# ESP8266.net
KiCad netlist of a schematic drawn in Altium Designer
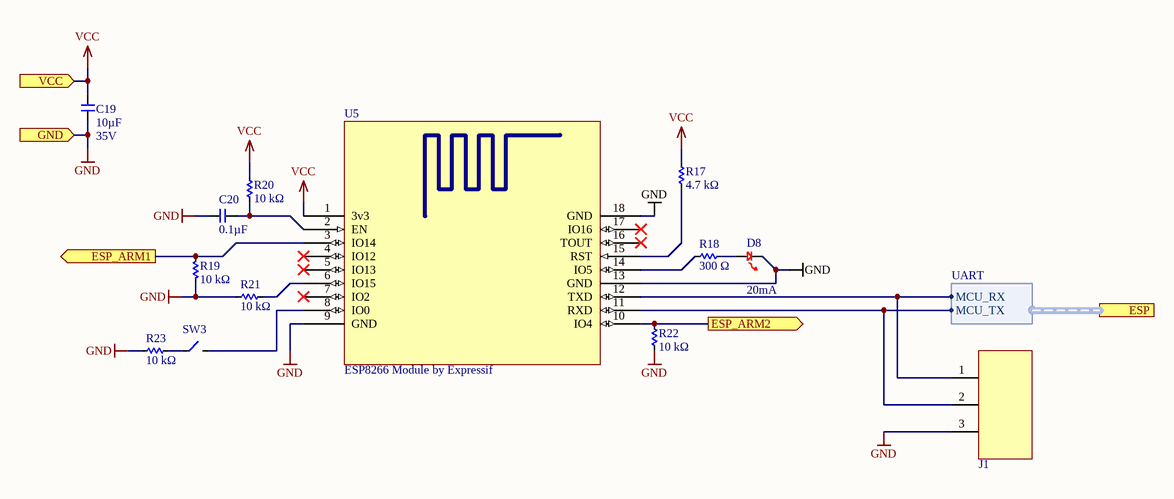
[diagram p0: ESP8266.SchDoc]

(export (version "E")
  (design (tool "Eeschema 10.0.6"))
  (components
    (comp (ref "C19")
      (value "__template_cap")
      (footprint "C0603")
      (description "CAP CER 10UF 35V X5R 0603 20%")
      (fields
        (field (name "CAPACITANCE (SHORTHAND)") "10µF")
        (field (name "RATED VOLTAGE") "35V")
        (field (name "MANUFACTURER") "Murata Electronics North America")
      )
      (libsource (lib "passives") (part "__template_cap"))
    )
    (comp (ref "C20")
      (value "__template_cap")
      (footprint "C0603")
      (fields
        (field (name "CAPACITANCE (SHORTHAND)") "0.1µF")
        (field (name "MANUFACTURER") "Murata Electronics North America")
      )
      (libsource (lib "passives") (part "__template_cap"))
    )
    (comp (ref "D8")
      (value "RED")
      (footprint "0805_Diode")
      (description "LED 0805 RED 20MA")
      (fields
        (field (name "MANUFACTURER") "OSRAM Opto Semiconductors Inc")
        (field (name "MANUFACTURER PART NUMBER") "LH R974-LP-1")
        (field (name "CURRENT - TEST") "20mA")
      )
      (libsource (lib "SSI") (part "LED_LY974"))
    )
    (comp (ref "J1")
      (value "CONN_1x3_RA_SMT_MALE_TSM-103-01-L-SH")
      (footprint "CONN_1x3_100MIL_RA_SMT")
      (description "CONN HEADER 3POS .100\" SNGL SMD")
      (fields
        (field (name "MANUFACTURER") "Samtec Inc.")
        (field (name "MANUFACTURER PART NUMBER") "TSM-103-01-L-SH")
      )
      (libsource (lib "SSI") (part "CONN_1x3_RA_SMT_MALE_TSM-103-01-L-SH"))
    )
    (comp (ref "R17")
      (value "__template_resistor")
      (footprint "R0603")
      (fields
        (field (name "MANUFACTURER") "Yageo")
        (field (name "RESISTANCE") "4.7 kΩ")
        (field (name "MANUFACTURER PART NUMBER") "RC0603FR-074K7L")
        (field (name "TOLERANCE") "±1%")
      )
      (libsource (lib "passives") (part "__template_resistor"))
    )
    (comp (ref "R18")
      (value "__template_resistor")
      (footprint "R0603")
      (fields
        (field (name "MANUFACTURER") "Yageo")
        (field (name "RESISTANCE") "300 Ω")
        (field (name "MANUFACTURER PART NUMBER") "RC0603FR-07300RL")
        (field (name "TOLERANCE") "±1%")
      )
      (libsource (lib "passives") (part "__template_resistor"))
    )
    (comp (ref "R19")
      (value "__template_resistor")
      (footprint "R0603")
      (fields
        (field (name "MANUFACTURER") "Yageo")
        (field (name "RESISTANCE") "10 kΩ")
        (field (name "MANUFACTURER PART NUMBER") "RC0603FR-0710KL")
        (field (name "TOLERANCE") "±1%")
      )
      (libsource (lib "passives") (part "__template_resistor"))
    )
    (comp (ref "R20")
      (value "__template_resistor")
      (footprint "R0603")
      (fields
        (field (name "MANUFACTURER") "Yageo")
        (field (name "RESISTANCE") "10 kΩ")
        (field (name "MANUFACTURER PART NUMBER") "RC0603FR-0710KL")
        (field (name "TOLERANCE") "±1%")
      )
      (libsource (lib "passives") (part "__template_resistor"))
    )
    (comp (ref "R21")
      (value "__template_resistor")
      (footprint "R0603")
      (fields
        (field (name "MANUFACTURER") "Yageo")
        (field (name "RESISTANCE") "10 kΩ")
        (field (name "MANUFACTURER PART NUMBER") "RC0603FR-0710KL")
        (field (name "TOLERANCE") "±1%")
      )
      (libsource (lib "passives") (part "__template_resistor"))
    )
    (comp (ref "R22")
      (value "__template_resistor")
      (footprint "R0603")
      (fields
        (field (name "MANUFACTURER") "Yageo")
        (field (name "RESISTANCE") "10 kΩ")
        (field (name "MANUFACTURER PART NUMBER") "RC0603FR-0710KL")
        (field (name "TOLERANCE") "±1%")
      )
      (libsource (lib "passives") (part "__template_resistor"))
    )
    (comp (ref "R23")
      (value "__template_resistor")
      (footprint "R0603")
      (fields
        (field (name "MANUFACTURER") "Yageo")
        (field (name "RESISTANCE") "10 kΩ")
        (field (name "MANUFACTURER PART NUMBER") "RC0603FR-0710KL")
        (field (name "TOLERANCE") "±1%")
      )
      (libsource (lib "passives") (part "__template_resistor"))
    )
    (comp (ref "SW3")
      (value "SWITCH_SPST-NO")
      (footprint "SWITCH_B3U-1000P")
      (description "SWITCH TACTILE SPST-NO 0.05A 12V")
      (fields
        (field (name "MANUFACTURER") "Omron Electronics Inc-EMC Div")
        (field (name "MANUFACTURER PART NUMBER") "B3U-1000P")
      )
      (libsource (lib "SSI") (part "SWITCH_SPST-NO"))
    )
    (comp (ref "U5")
      (value "ESP8266 Module by Expressif")
      (footprint "ESP-WROOM-02")
      (fields (field (name "PUBLISHER") "SSI") (field (name "LATESTREVIEWER") "Tim Vrakas"))
      (libsource (lib "SSI") (part "ESP-WROOM-02"))
    )
  )
  (nets
    (net (code "2") (name "/ESP_ARM1") (class "Default")
      (node (ref "R19") (pin "1") (pintype "passive"))
      (node (ref "U5") (pin "3") (pinfunction "IO14_3") (pintype "bidirectional"))
    )
    (net (code "3") (name "/ESP_ARM2") (class "Default")
      (node (ref "R22") (pin "1") (pintype "passive"))
      (node (ref "U5") (pin "10") (pinfunction "IO4_10") (pintype "bidirectional"))
    )
    (net (code "5") (name "GND") (class "Default")
      (node (ref "C19") (pin "2") (pintype "passive"))
      (node (ref "C20") (pin "1") (pintype "passive"))
      (node (ref "D8") (pin "1") (pintype "passive"))
      (node (ref "J1") (pin "3") (pinfunction "3_3") (pintype "passive"))
      (node (ref "R19") (pin "2") (pintype "passive"))
      (node (ref "R21") (pin "2") (pintype "passive"))
      (node (ref "R22") (pin "2") (pintype "passive"))
      (node (ref "R23") (pin "2") (pintype "passive"))
      (node (ref "U5") (pin "13") (pinfunction "GND_13") (pintype "power_in"))
      (node (ref "U5") (pin "18") (pinfunction "GND_18") (pintype "power_in"))
      (node (ref "U5") (pin "9") (pinfunction "GND_9") (pintype "power_in"))
    )
    (net (code "6") (name "Net-(D8-Pad2)") (class "Default")
      (node (ref "D8") (pin "2") (pintype "passive"))
      (node (ref "R18") (pin "2") (pintype "passive"))
    )
    (net (code "7") (name "Net-(R23-Pad1)") (class "Default")
      (node (ref "R23") (pin "1") (pintype "passive"))
      (node (ref "SW3") (pin "1") (pintype "passive"))
    )
    (net (code "8") (name "Net-(U5-EN)") (class "Default")
      (node (ref "C20") (pin "2") (pintype "passive"))
      (node (ref "R20") (pin "1") (pintype "passive"))
      (node (ref "U5") (pin "2") (pinfunction "EN_2") (pintype "input"))
    )
    (net (code "9") (name "Net-(U5-IO0)") (class "Default")
      (node (ref "SW3") (pin "2") (pintype "passive"))
      (node (ref "U5") (pin "8") (pinfunction "IO0_8") (pintype "bidirectional"))
    )
    (net (code "10") (name "Net-(U5-IO5)") (class "Default")
      (node (ref "R18") (pin "1") (pintype "passive"))
      (node (ref "U5") (pin "14") (pinfunction "IO5_14") (pintype "bidirectional"))
    )
    (net (code "11") (name "Net-(U5-IO15)") (class "Default")
      (node (ref "R21") (pin "1") (pintype "passive"))
      (node (ref "U5") (pin "6") (pinfunction "IO15_6") (pintype "bidirectional"))
    )
    (net (code "12") (name "Net-(U5-RST)") (class "Default")
      (node (ref "R17") (pin "1") (pintype "passive"))
      (node (ref "U5") (pin "15") (pinfunction "RST_15") (pintype "input"))
    )
    (net (code "13") (name "Net-(U5-RXD)") (class "Default")
      (node (ref "J1") (pin "2") (pinfunction "2_2") (pintype "passive"))
      (node (ref "U5") (pin "11") (pinfunction "RXD_11") (pintype "bidirectional"))
    )
    (net (code "14") (name "Net-(U5-TXD)") (class "Default")
      (node (ref "J1") (pin "1") (pinfunction "1_1") (pintype "passive"))
      (node (ref "U5") (pin "12") (pinfunction "TXD_12") (pintype "bidirectional"))
    )
    (net (code "15") (name "VCC") (class "Default")
      (node (ref "C19") (pin "1") (pintype "passive"))
      (node (ref "R17") (pin "2") (pintype "passive"))
      (node (ref "R20") (pin "2") (pintype "passive"))
      (node (ref "U5") (pin "1") (pinfunction "3v3_1") (pintype "power_in"))
    )
    (net (code "16") (name "unconnected-(U5-IO2-Pad7)") (class "Default")
      (node (ref "U5") (pin "7") (pinfunction "IO2_7") (pintype "bidirectional+no_connect"))
    )
    (net (code "17") (name "unconnected-(U5-IO12-Pad4)") (class "Default")
      (node (ref "U5") (pin "4") (pinfunction "IO12_4") (pintype "bidirectional+no_connect"))
    )
    (net (code "18") (name "unconnected-(U5-IO13-Pad5)") (class "Default")
      (node (ref "U5") (pin "5") (pinfunction "IO13_5") (pintype "bidirectional+no_connect"))
    )
    (net (code "19") (name "unconnected-(U5-IO16-Pad17)") (class "Default")
      (node (ref "U5") (pin "17") (pinfunction "IO16_17") (pintype "bidirectional+no_connect"))
    )
    (net (code "20") (name "unconnected-(U5-TOUT-Pad16)") (class "Default")
      (node (ref "U5") (pin "16") (pinfunction "TOUT_16") (pintype "bidirectional+no_connect"))
    )
  )
)
